# 5-ADC.net
KiCad netlist of a schematic drawn in Altium Designer
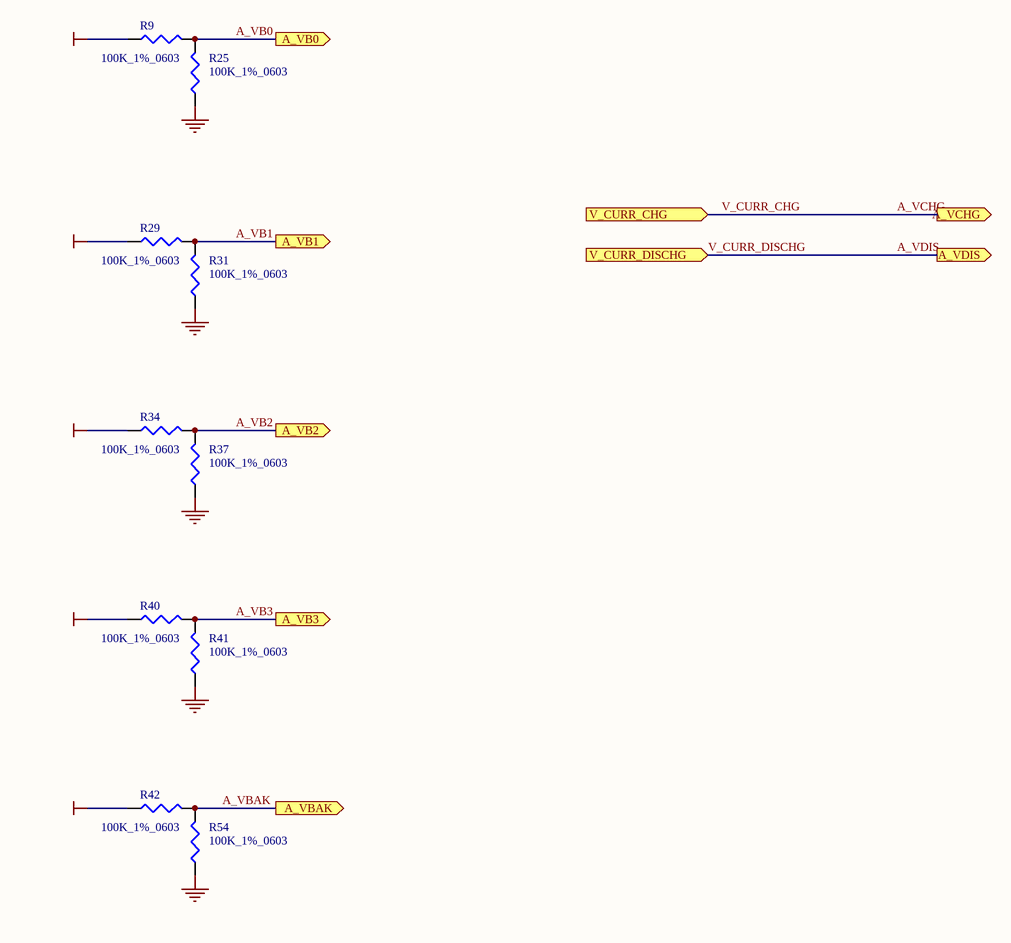
[diagram p0: 5-ADC.SCHDOC]

(export (version "E")
  (design (tool "Eeschema 10.0.6"))
  (components
    (comp (ref "R9")
      (value "100K_1%_0603")
      (footprint "C1608-0603")
      (description "Resistor")
      (fields (field (name "PUBLISHER") "Altium Limited"))
      (libsource (lib "Miscellaneous Devices") (part "Res3"))
    )
    (comp (ref "R25")
      (value "100K_1%_0603")
      (footprint "C1608-0603")
      (description "Resistor")
      (fields (field (name "PUBLISHER") "Altium Limited"))
      (libsource (lib "Miscellaneous Devices") (part "Res3"))
    )
    (comp (ref "R29")
      (value "100K_1%_0603")
      (footprint "C1608-0603")
      (description "Resistor")
      (fields (field (name "PUBLISHER") "Altium Limited"))
      (libsource (lib "Miscellaneous Devices") (part "Res3"))
    )
    (comp (ref "R31")
      (value "100K_1%_0603")
      (footprint "C1608-0603")
      (description "Resistor")
      (fields (field (name "PUBLISHER") "Altium Limited"))
      (libsource (lib "Miscellaneous Devices") (part "Res3"))
    )
    (comp (ref "R34")
      (value "100K_1%_0603")
      (footprint "C1608-0603")
      (description "Resistor")
      (fields (field (name "PUBLISHER") "Altium Limited"))
      (libsource (lib "Miscellaneous Devices") (part "Res3"))
    )
    (comp (ref "R37")
      (value "100K_1%_0603")
      (footprint "C1608-0603")
      (description "Resistor")
      (fields (field (name "PUBLISHER") "Altium Limited"))
      (libsource (lib "Miscellaneous Devices") (part "Res3"))
    )
    (comp (ref "R40")
      (value "100K_1%_0603")
      (footprint "C1608-0603")
      (description "Resistor")
      (fields (field (name "PUBLISHER") "Altium Limited"))
      (libsource (lib "Miscellaneous Devices") (part "Res3"))
    )
    (comp (ref "R41")
      (value "100K_1%_0603")
      (footprint "C1608-0603")
      (description "Resistor")
      (fields (field (name "PUBLISHER") "Altium Limited"))
      (libsource (lib "Miscellaneous Devices") (part "Res3"))
    )
    (comp (ref "R42")
      (value "100K_1%_0603")
      (footprint "C1608-0603")
      (description "Resistor")
      (fields (field (name "PUBLISHER") "Altium Limited"))
      (libsource (lib "Miscellaneous Devices") (part "Res3"))
    )
    (comp (ref "R54")
      (value "100K_1%_0603")
      (footprint "C1608-0603")
      (description "Resistor")
      (fields (field (name "PUBLISHER") "Altium Limited"))
      (libsource (lib "Miscellaneous Devices") (part "Res3"))
    )
  )
  (nets
    (net (code "1") (name "/A_VB0") (class "Default")
      (node (ref "R25") (pin "2") (pinfunction "2_2") (pintype "passive"))
      (node (ref "R9") (pin "2") (pinfunction "2_2") (pintype "passive"))
    )
    (net (code "2") (name "/A_VB1") (class "Default")
      (node (ref "R29") (pin "2") (pinfunction "2_2") (pintype "passive"))
      (node (ref "R31") (pin "2") (pinfunction "2_2") (pintype "passive"))
    )
    (net (code "3") (name "/A_VB2") (class "Default")
      (node (ref "R34") (pin "2") (pinfunction "2_2") (pintype "passive"))
      (node (ref "R37") (pin "2") (pinfunction "2_2") (pintype "passive"))
    )
    (net (code "4") (name "/A_VB3") (class "Default")
      (node (ref "R40") (pin "2") (pinfunction "2_2") (pintype "passive"))
      (node (ref "R41") (pin "2") (pinfunction "2_2") (pintype "passive"))
    )
    (net (code "5") (name "/A_VBAK") (class "Default")
      (node (ref "R42") (pin "2") (pinfunction "2_2") (pintype "passive"))
      (node (ref "R54") (pin "2") (pinfunction "2_2") (pintype "passive"))
    )
    (net (code "8") (name "GND") (class "Default")
      (node (ref "R25") (pin "1") (pinfunction "1_1") (pintype "passive"))
      (node (ref "R31") (pin "1") (pinfunction "1_1") (pintype "passive"))
      (node (ref "R37") (pin "1") (pinfunction "1_1") (pintype "passive"))
      (node (ref "R41") (pin "1") (pinfunction "1_1") (pintype "passive"))
      (node (ref "R54") (pin "1") (pinfunction "1_1") (pintype "passive"))
    )
    (net (code "9") (name "V_BAK") (class "Default")
      (node (ref "R42") (pin "1") (pinfunction "1_1") (pintype "passive"))
    )
    (net (code "10") (name "V_BT0") (class "Default")
      (node (ref "R9") (pin "1") (pinfunction "1_1") (pintype "passive"))
    )
    (net (code "11") (name "V_BT1") (class "Default")
      (node (ref "R29") (pin "1") (pinfunction "1_1") (pintype "passive"))
    )
    (net (code "12") (name "V_BT2") (class "Default")
      (node (ref "R34") (pin "1") (pinfunction "1_1") (pintype "passive"))
    )
    (net (code "13") (name "V_BT3") (class "Default")
      (node (ref "R40") (pin "1") (pinfunction "1_1") (pintype "passive"))
    )
  )
)
